# Sheet2.net
KiCad netlist of a schematic drawn in Altium Designer
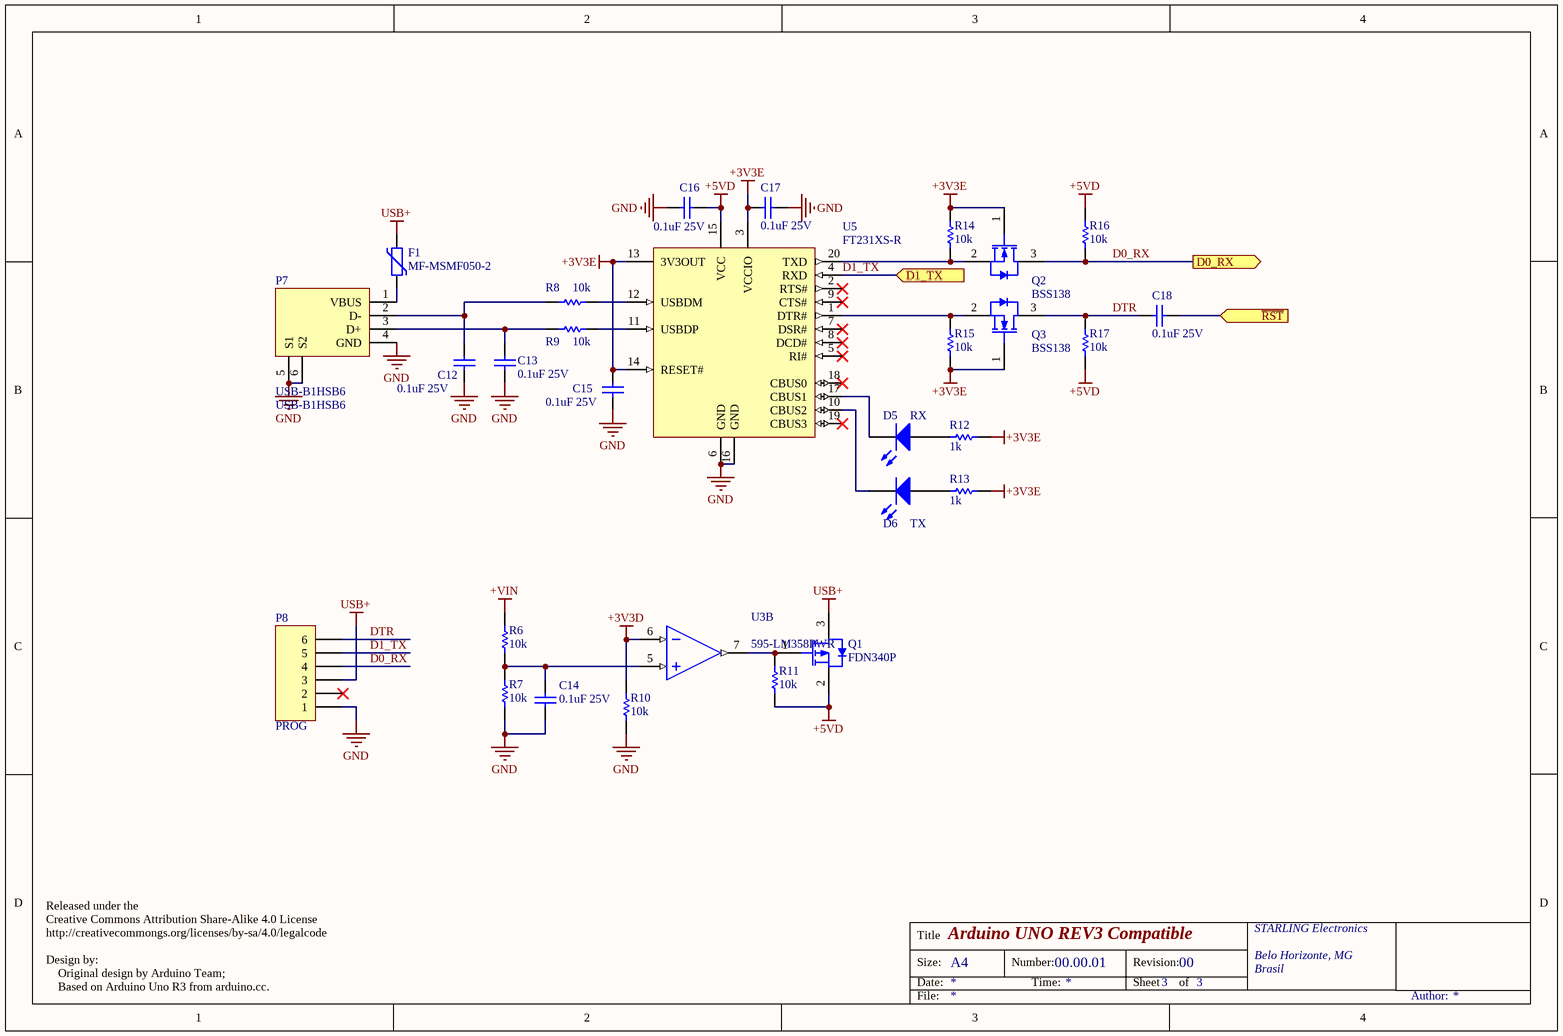
[diagram p0: Sheet2.SchDoc]

(export (version "E")
  (design (tool "Eeschema 10.0.6"))
  (components
    (comp (ref "C12")
      (value "0.1uF 25V")
      (footprint "C1608[0603]")
      (description "Capacitor")
      (fields (field (name "MANUFACTURER PART NUMBER") "GCM188R71E104KA57D") (field (name "TOLERANCE") "10%"))
      (libsource (lib "Basic Library") (part "C"))
    )
    (comp (ref "C13")
      (value "0.1uF 25V")
      (footprint "C1608[0603]")
      (description "Capacitor")
      (fields (field (name "MANUFACTURER PART NUMBER") "GCM188R71E104KA57D") (field (name "TOLERANCE") "10%"))
      (libsource (lib "Basic Library") (part "C"))
    )
    (comp (ref "C14")
      (value "0.1uF 25V")
      (footprint "C1608[0603]")
      (description "Capacitor")
      (fields (field (name "MANUFACTURER PART NUMBER") "GCM188R71E104KA57D") (field (name "TOLERANCE") "10%"))
      (libsource (lib "Basic Library") (part "C"))
    )
    (comp (ref "C15")
      (value "0.1uF 25V")
      (footprint "C1608[0603]")
      (description "Capacitor")
      (fields (field (name "MANUFACTURER PART NUMBER") "GCM188R71E104KA57D") (field (name "TOLERANCE") "10%"))
      (libsource (lib "Basic Library") (part "C"))
    )
    (comp (ref "C16")
      (value "0.1uF 25V")
      (footprint "C1608[0603]")
      (description "Capacitor")
      (fields (field (name "MANUFACTURER PART NUMBER") "GCM188R71E104KA57D") (field (name "TOLERANCE") "10%"))
      (libsource (lib "Basic Library") (part "C"))
    )
    (comp (ref "C17")
      (value "0.1uF 25V")
      (footprint "C1608[0603]")
      (description "Capacitor")
      (fields (field (name "MANUFACTURER PART NUMBER") "GCM188R71E104KA57D") (field (name "TOLERANCE") "10%"))
      (libsource (lib "Basic Library") (part "C"))
    )
    (comp (ref "C18")
      (value "0.1uF 25V")
      (footprint "C1608[0603]")
      (description "Capacitor")
      (fields (field (name "MANUFACTURER PART NUMBER") "GCM188R71E104KA57D") (field (name "TOLERANCE") "10%"))
      (libsource (lib "Basic Library") (part "C"))
    )
    (comp (ref "D5")
      (value "RX")
      (footprint "LED-0603-R")
      (description "LED")
      (fields (field (name "MANUFACTURER PART NUMBER") "LTST-C190KSKT"))
      (libsource (lib "Basic Library") (part "LED"))
    )
    (comp (ref "D6")
      (value "TX")
      (footprint "LED-0603-R")
      (description "LED")
      (fields (field (name "MANUFACTURER PART NUMBER") "LTST-C190KSKT"))
      (libsource (lib "Basic Library") (part "LED"))
    )
    (comp (ref "F1")
      (value "MF-MSMF050-2")
      (footprint "MF-MSMF050")
      (description "Resettable Fuse")
      (libsource (lib "Components Library") (part "MF-MSMF050-2"))
    )
    (comp (ref "P7")
      (value "USB-B1HSB6")
      (footprint "USB_Type_B")
      (description "Conn USB Type B RCP 4 POS 2.5mm Solder RA Thru-Hole 4 Terminal 1 Port")
      (fields
        (field (name "MANUFACTURER") "On-Shore Technology")
        (field (name "SUPPLIER PART NUMBER 1") "USB-B1HSB6")
      )
      (libsource (lib "Connectors Library") (part "USB Type B"))
    )
    (comp (ref "P8")
      (value "PROG")
      (footprint "HDR1X6m")
      (description "Header, 6-Pin")
      (fields
        (field (name "MANUFACTURER") "Amphenol FCI")
        (field (name "MANUFACTURER PART NUMBER") "68000-406HLF")
        (field (name "PUBLISHER") "Altium Limited")
      )
      (libsource (lib "Connectors Library") (part "Header 6"))
    )
    (comp (ref "Q1")
      (value "FDN340P")
      (footprint "SOT23")
      (description "P-Channel MOSFET")
      (libsource (lib "Basic Library") (part "MOSFET-P"))
    )
    (comp (ref "Q2")
      (value "BSS138")
      (footprint "SOT23")
      (description "N-Channel MOSFET")
      (libsource (lib "Basic Library") (part "MOSFET-N"))
    )
    (comp (ref "Q3")
      (value "BSS138")
      (footprint "SOT23")
      (description "N-Channel MOSFET")
      (libsource (lib "Basic Library") (part "MOSFET-N"))
    )
    (comp (ref "R6")
      (value "10k")
      (footprint "R1608[0603]")
      (description "Resistor")
      (fields (field (name "MANUFACTURER PART NUMBER") "MCT06030C1002FP500") (field (name "TOLERANCE") "1%"))
      (libsource (lib "Basic Library") (part "R"))
    )
    (comp (ref "R7")
      (value "10k")
      (footprint "R1608[0603]")
      (description "Resistor")
      (fields (field (name "MANUFACTURER PART NUMBER") "MCT06030C1002FP500") (field (name "TOLERANCE") "1%"))
      (libsource (lib "Basic Library") (part "R"))
    )
    (comp (ref "R8")
      (value "10k")
      (footprint "R1608[0603]")
      (description "Resistor")
      (fields (field (name "MANUFACTURER PART NUMBER") "MCT06030C1002FP500") (field (name "TOLERANCE") "1%"))
      (libsource (lib "Basic Library") (part "R"))
    )
    (comp (ref "R9")
      (value "10k")
      (footprint "R1608[0603]")
      (description "Resistor")
      (fields (field (name "MANUFACTURER PART NUMBER") "MCT06030C1002FP500") (field (name "TOLERANCE") "1%"))
      (libsource (lib "Basic Library") (part "R"))
    )
    (comp (ref "R10")
      (value "10k")
      (footprint "R1608[0603]")
      (description "Resistor")
      (fields (field (name "MANUFACTURER PART NUMBER") "MCT06030C1002FP500") (field (name "TOLERANCE") "1%"))
      (libsource (lib "Basic Library") (part "R"))
    )
    (comp (ref "R11")
      (value "10k")
      (footprint "R1608[0603]")
      (description "Resistor")
      (fields (field (name "MANUFACTURER PART NUMBER") "MCT06030C1002FP500") (field (name "TOLERANCE") "1%"))
      (libsource (lib "Basic Library") (part "R"))
    )
    (comp (ref "R12")
      (value "1k")
      (footprint "R1608[0603]")
      (description "Resistor")
      (fields (field (name "MANUFACTURER PART NUMBER") "ESR03EZPJ102") (field (name "TOLERANCE") "5%"))
      (libsource (lib "Basic Library") (part "R"))
    )
    (comp (ref "R13")
      (value "1k")
      (footprint "R1608[0603]")
      (description "Resistor")
      (fields (field (name "MANUFACTURER PART NUMBER") "ESR03EZPJ102") (field (name "TOLERANCE") "5%"))
      (libsource (lib "Basic Library") (part "R"))
    )
    (comp (ref "R14")
      (value "10k")
      (footprint "R1608[0603]")
      (description "Resistor")
      (fields (field (name "MANUFACTURER PART NUMBER") "MCT06030C1002FP500") (field (name "TOLERANCE") "1%"))
      (libsource (lib "Basic Library") (part "R"))
    )
    (comp (ref "R15")
      (value "10k")
      (footprint "R1608[0603]")
      (description "Resistor")
      (fields (field (name "MANUFACTURER PART NUMBER") "MCT06030C1002FP500") (field (name "TOLERANCE") "1%"))
      (libsource (lib "Basic Library") (part "R"))
    )
    (comp (ref "R16")
      (value "10k")
      (footprint "R1608[0603]")
      (description "Resistor")
      (fields (field (name "MANUFACTURER PART NUMBER") "MCT06030C1002FP500") (field (name "TOLERANCE") "1%"))
      (libsource (lib "Basic Library") (part "R"))
    )
    (comp (ref "R17")
      (value "10k")
      (footprint "R1608[0603]")
      (description "Resistor")
      (fields (field (name "MANUFACTURER PART NUMBER") "MCT06030C1002FP500") (field (name "TOLERANCE") "1%"))
      (libsource (lib "Basic Library") (part "R"))
    )
    (comp (ref "U3")
      (value "AMP Op")
      (footprint "TSSOP8-1")
      (description "IC OPAMP GP 700KHZ 8TSSOP")
      (fields
        (field (name "MANUFACTURER") "Texas Instruments")
        (field (name "MANUFACTURER PART NUMBER") "LM358PWR")
        (field (name "SUPPLIER PART NUMBER 1") "595-LM358PWR")
      )
      (libsource (lib "Components Library") (part "LM358PWR"))
    )
    (comp (ref "U5")
      (value "FT231XS-R")
      (footprint "NSSOP-20_N")
      (fields (field (name "MANUFACTURER") "FTDI"))
      (libsource (lib "Components Library") (part "FT231XS-R"))
    )
  )
  (nets
    (net (code "1") (name "+3V3D") (class "Default")
      (node (ref "R10") (pin "1") (pinfunction "1_1") (pintype "passive"))
      (node (ref "U3") (pin "6") (pinfunction "IN-_6") (pintype "input"))
    )
    (net (code "2") (name "+3V3E") (class "Default")
      (node (ref "C15") (pin "2") (pinfunction "2_2") (pintype "passive"))
      (node (ref "C17") (pin "2") (pinfunction "2_2") (pintype "passive"))
      (node (ref "Q2") (pin "1") (pinfunction "GATE_1") (pintype "passive"))
      (node (ref "Q3") (pin "1") (pinfunction "GATE_1") (pintype "passive"))
      (node (ref "R12") (pin "2") (pinfunction "2_2") (pintype "passive"))
      (node (ref "R13") (pin "2") (pinfunction "2_2") (pintype "passive"))
      (node (ref "R14") (pin "1") (pinfunction "1_1") (pintype "passive"))
      (node (ref "R15") (pin "2") (pinfunction "2_2") (pintype "passive"))
      (node (ref "U5") (pin "13") (pinfunction "3V3OUT_13") (pintype "power_in"))
      (node (ref "U5") (pin "14") (pinfunction "RESET#_14") (pintype "input"))
      (node (ref "U5") (pin "3") (pinfunction "VCCIO_3") (pintype "power_in"))
    )
    (net (code "3") (name "+5VD") (class "Default")
      (node (ref "C16") (pin "1") (pinfunction "1_1") (pintype "passive"))
      (node (ref "Q1") (pin "2") (pinfunction "SOURCE_2") (pintype "passive"))
      (node (ref "R11") (pin "2") (pinfunction "2_2") (pintype "passive"))
      (node (ref "R16") (pin "1") (pinfunction "1_1") (pintype "passive"))
      (node (ref "R17") (pin "2") (pinfunction "2_2") (pintype "passive"))
      (node (ref "U5") (pin "15") (pinfunction "VCC_15") (pintype "power_in"))
    )
    (net (code "4") (name "+VIN") (class "Default")
      (node (ref "R6") (pin "1") (pinfunction "1_1") (pintype "passive"))
    )
    (net (code "5") (name "/D0_RX") (class "Default")
      (node (ref "P8") (pin "4") (pinfunction "4_4") (pintype "passive"))
      (node (ref "Q2") (pin "3") (pinfunction "DRAIN_3") (pintype "passive"))
      (node (ref "R16") (pin "2") (pinfunction "2_2") (pintype "passive"))
    )
    (net (code "6") (name "/D1_TX") (class "Default")
      (node (ref "P8") (pin "5") (pinfunction "5_5") (pintype "passive"))
      (node (ref "U5") (pin "4") (pinfunction "RXD_4") (pintype "input"))
    )
    (net (code "7") (name "/DTR") (class "Default")
      (node (ref "C18") (pin "1") (pinfunction "1_1") (pintype "passive"))
      (node (ref "P8") (pin "6") (pinfunction "6_6") (pintype "passive"))
      (node (ref "Q3") (pin "3") (pinfunction "DRAIN_3") (pintype "passive"))
      (node (ref "R17") (pin "1") (pinfunction "1_1") (pintype "passive"))
    )
    (net (code "8") (name "/~{RST}") (class "Default")
      (node (ref "C18") (pin "2") (pinfunction "2_2") (pintype "passive"))
    )
    (net (code "9") (name "GND") (class "Default")
      (node (ref "C12") (pin "2") (pinfunction "2_2") (pintype "passive"))
      (node (ref "C13") (pin "2") (pinfunction "2_2") (pintype "passive"))
      (node (ref "C14") (pin "1") (pinfunction "1_1") (pintype "passive"))
      (node (ref "C15") (pin "1") (pinfunction "1_1") (pintype "passive"))
      (node (ref "C16") (pin "2") (pinfunction "2_2") (pintype "passive"))
      (node (ref "C17") (pin "1") (pinfunction "1_1") (pintype "passive"))
      (node (ref "P7") (pin "4") (pinfunction "GND_4") (pintype "passive"))
      (node (ref "P7") (pin "5") (pinfunction "S1_5") (pintype "passive"))
      (node (ref "P7") (pin "6") (pinfunction "S2_6") (pintype "passive"))
      (node (ref "P8") (pin "1") (pinfunction "1_1") (pintype "passive"))
      (node (ref "R10") (pin "2") (pinfunction "2_2") (pintype "passive"))
      (node (ref "R7") (pin "2") (pinfunction "2_2") (pintype "passive"))
      (node (ref "U5") (pin "16") (pinfunction "GND_16") (pintype "power_in"))
      (node (ref "U5") (pin "6") (pinfunction "GND_6") (pintype "power_in"))
    )
    (net (code "10") (name "Net-(D5-A)") (class "Default")
      (node (ref "D5") (pin "1") (pinfunction "A_1") (pintype "passive"))
      (node (ref "R12") (pin "1") (pinfunction "1_1") (pintype "passive"))
    )
    (net (code "11") (name "Net-(D5-K)") (class "Default")
      (node (ref "D5") (pin "2") (pinfunction "K_2") (pintype "passive"))
      (node (ref "U5") (pin "17") (pinfunction "CBUS1_17") (pintype "bidirectional"))
    )
    (net (code "12") (name "Net-(D6-A)") (class "Default")
      (node (ref "D6") (pin "1") (pinfunction "A_1") (pintype "passive"))
      (node (ref "R13") (pin "1") (pinfunction "1_1") (pintype "passive"))
    )
    (net (code "13") (name "Net-(D6-K)") (class "Default")
      (node (ref "D6") (pin "2") (pinfunction "K_2") (pintype "passive"))
      (node (ref "U5") (pin "10") (pinfunction "CBUS2_10") (pintype "bidirectional"))
    )
    (net (code "14") (name "Net-(P7-D+)") (class "Default")
      (node (ref "C13") (pin "1") (pinfunction "1_1") (pintype "passive"))
      (node (ref "P7") (pin "3") (pinfunction "D+_3") (pintype "passive"))
      (node (ref "R9") (pin "2") (pinfunction "2_2") (pintype "passive"))
    )
    (net (code "15") (name "Net-(P7-D-)") (class "Default")
      (node (ref "C12") (pin "1") (pinfunction "1_1") (pintype "passive"))
      (node (ref "P7") (pin "2") (pinfunction "D-_2") (pintype "passive"))
      (node (ref "R8") (pin "2") (pinfunction "2_2") (pintype "passive"))
    )
    (net (code "16") (name "Net-(P7-VBUS)") (class "Default")
      (node (ref "F1") (pin "1") (pinfunction "1_1") (pintype "passive"))
      (node (ref "P7") (pin "1") (pinfunction "VBUS_1") (pintype "passive"))
    )
    (net (code "17") (name "Net-(Q1-GATE)") (class "Default")
      (node (ref "Q1") (pin "1") (pinfunction "GATE_1") (pintype "passive"))
      (node (ref "R11") (pin "1") (pinfunction "1_1") (pintype "passive"))
      (node (ref "U3") (pin "7") (pinfunction "OUT_7") (pintype "output"))
    )
    (net (code "18") (name "Net-(Q2-SOURCE)") (class "Default")
      (node (ref "Q2") (pin "2") (pinfunction "SOURCE_2") (pintype "passive"))
      (node (ref "R14") (pin "2") (pinfunction "2_2") (pintype "passive"))
      (node (ref "U5") (pin "20") (pinfunction "TXD_20") (pintype "output"))
    )
    (net (code "19") (name "Net-(Q3-SOURCE)") (class "Default")
      (node (ref "Q3") (pin "2") (pinfunction "SOURCE_2") (pintype "passive"))
      (node (ref "R15") (pin "1") (pinfunction "1_1") (pintype "passive"))
      (node (ref "U5") (pin "1") (pinfunction "DTR#_1") (pintype "output"))
    )
    (net (code "20") (name "Net-(U3B-IN+)") (class "Default")
      (node (ref "C14") (pin "2") (pinfunction "2_2") (pintype "passive"))
      (node (ref "R6") (pin "2") (pinfunction "2_2") (pintype "passive"))
      (node (ref "R7") (pin "1") (pinfunction "1_1") (pintype "passive"))
      (node (ref "U3") (pin "5") (pinfunction "IN+_5") (pintype "input"))
    )
    (net (code "21") (name "Net-(U5-USBDM)") (class "Default")
      (node (ref "R8") (pin "1") (pinfunction "1_1") (pintype "passive"))
      (node (ref "U5") (pin "12") (pinfunction "USBDM_12") (pintype "input"))
    )
    (net (code "22") (name "Net-(U5-USBDP)") (class "Default")
      (node (ref "R9") (pin "1") (pinfunction "1_1") (pintype "passive"))
      (node (ref "U5") (pin "11") (pinfunction "USBDP_11") (pintype "input"))
    )
    (net (code "23") (name "USB+") (class "Default")
      (node (ref "F1") (pin "2") (pinfunction "2_2") (pintype "passive"))
      (node (ref "P8") (pin "3") (pinfunction "3_3") (pintype "passive"))
      (node (ref "Q1") (pin "3") (pinfunction "DRAIN_3") (pintype "passive"))
    )
    (net (code "24") (name "unconnected-(P8-Pad2)") (class "Default")
      (node (ref "P8") (pin "2") (pinfunction "2_2") (pintype "passive+no_connect"))
    )
    (net (code "25") (name "unconnected-(U5-CBUS0-Pad18)") (class "Default")
      (node (ref "U5") (pin "18") (pinfunction "CBUS0_18") (pintype "bidirectional+no_connect"))
    )
    (net (code "26") (name "unconnected-(U5-CBUS3-Pad19)") (class "Default")
      (node (ref "U5") (pin "19") (pinfunction "CBUS3_19") (pintype "bidirectional+no_connect"))
    )
    (net (code "27") (name "unconnected-(U5-CTS#-Pad9)") (class "Default")
      (node (ref "U5") (pin "9") (pinfunction "CTS#_9") (pintype "input+no_connect"))
    )
    (net (code "28") (name "unconnected-(U5-DCD#-Pad8)") (class "Default")
      (node (ref "U5") (pin "8") (pinfunction "DCD#_8") (pintype "input+no_connect"))
    )
    (net (code "29") (name "unconnected-(U5-DSR#-Pad7)") (class "Default")
      (node (ref "U5") (pin "7") (pinfunction "DSR#_7") (pintype "input+no_connect"))
    )
    (net (code "30") (name "unconnected-(U5-RI#-Pad5)") (class "Default")
      (node (ref "U5") (pin "5") (pinfunction "RI#_5") (pintype "input+no_connect"))
    )
    (net (code "31") (name "unconnected-(U5-RTS#-Pad2)") (class "Default")
      (node (ref "U5") (pin "2") (pinfunction "RTS#_2") (pintype "output+no_connect"))
    )
  )
)
